# I2C_board_Schematic.net
KiCad netlist of a schematic drawn in Altium Designer
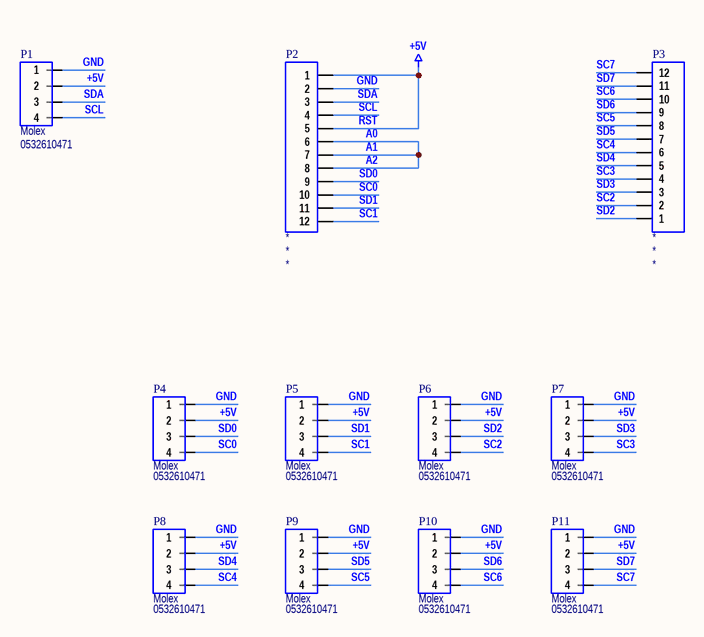
[diagram p0: I2C_board_Schematic.SchDoc]

(export (version "E")
  (design (tool "Eeschema 10.0.6"))
  (components
    (comp (ref "P1")
      (value "CONN MOLEX 53261-0471 (father)")
      (footprint "CONN MOLEX 53261-0471 (father)")
      (fields (field (name "MANUFACTURER") "Molex") (field (name "MODEL") "0532610471"))
      (libsource (lib "ADLibrary_Library") (part "CONN MOLEX 53261-0471 (father)"))
    )
    (comp (ref "P2")
      (value "Connector 1x12 0.1\"")
      (footprint "CONN-12 1x12 MALE")
      (fields (field (name "CASE") "*") (field (name "ALTIUM_VALUE") "*") (field (name "MODEL") "*"))
      (libsource (lib "ADLibrary_Library") (part "Connector 1x12 0.1{dblquote}"))
    )
    (comp (ref "P3")
      (value "Connector 1x12 0.1\"")
      (footprint "CONN-12 1x12 MALE")
      (fields (field (name "CASE") "*") (field (name "ALTIUM_VALUE") "*") (field (name "MODEL") "*"))
      (libsource (lib "") (part "Connector 1x12 0.1{dblquote}_1"))
    )
    (comp (ref "P4")
      (value "CONN MOLEX 53261-0471 (father)")
      (footprint "CONN MOLEX 53261-0471 (father)")
      (fields (field (name "MANUFACTURER") "Molex") (field (name "MODEL") "0532610471"))
      (libsource (lib "ADLibrary_Library") (part "CONN MOLEX 53261-0471 (father)"))
    )
    (comp (ref "P5")
      (value "CONN MOLEX 53261-0471 (father)")
      (footprint "CONN MOLEX 53261-0471 (father)")
      (fields (field (name "MANUFACTURER") "Molex") (field (name "MODEL") "0532610471"))
      (libsource (lib "ADLibrary_Library") (part "CONN MOLEX 53261-0471 (father)"))
    )
    (comp (ref "P6")
      (value "CONN MOLEX 53261-0471 (father)")
      (footprint "CONN MOLEX 53261-0471 (father)")
      (fields (field (name "MANUFACTURER") "Molex") (field (name "MODEL") "0532610471"))
      (libsource (lib "ADLibrary_Library") (part "CONN MOLEX 53261-0471 (father)"))
    )
    (comp (ref "P7")
      (value "CONN MOLEX 53261-0471 (father)")
      (footprint "CONN MOLEX 53261-0471 (father)")
      (fields (field (name "MANUFACTURER") "Molex") (field (name "MODEL") "0532610471"))
      (libsource (lib "ADLibrary_Library") (part "CONN MOLEX 53261-0471 (father)"))
    )
    (comp (ref "P8")
      (value "CONN MOLEX 53261-0471 (father)")
      (footprint "CONN MOLEX 53261-0471 (father)")
      (fields (field (name "MANUFACTURER") "Molex") (field (name "MODEL") "0532610471"))
      (libsource (lib "ADLibrary_Library") (part "CONN MOLEX 53261-0471 (father)"))
    )
    (comp (ref "P9")
      (value "CONN MOLEX 53261-0471 (father)")
      (footprint "CONN MOLEX 53261-0471 (father)")
      (fields (field (name "MANUFACTURER") "Molex") (field (name "MODEL") "0532610471"))
      (libsource (lib "ADLibrary_Library") (part "CONN MOLEX 53261-0471 (father)"))
    )
    (comp (ref "P10")
      (value "CONN MOLEX 53261-0471 (father)")
      (footprint "CONN MOLEX 53261-0471 (father)")
      (fields (field (name "MANUFACTURER") "Molex") (field (name "MODEL") "0532610471"))
      (libsource (lib "ADLibrary_Library") (part "CONN MOLEX 53261-0471 (father)"))
    )
    (comp (ref "P11")
      (value "CONN MOLEX 53261-0471 (father)")
      (footprint "CONN MOLEX 53261-0471 (father)")
      (fields (field (name "MANUFACTURER") "Molex") (field (name "MODEL") "0532610471"))
      (libsource (lib "ADLibrary_Library") (part "CONN MOLEX 53261-0471 (father)"))
    )
  )
  (nets
    (net (code "1") (name "+5V") (class "Default")
      (node (ref "P1") (pin "2") (pinfunction "2_2") (pintype "passive"))
      (node (ref "P10") (pin "2") (pinfunction "2_2") (pintype "passive"))
      (node (ref "P11") (pin "2") (pinfunction "2_2") (pintype "passive"))
      (node (ref "P2") (pin "1") (pinfunction "1_1") (pintype "passive"))
      (node (ref "P2") (pin "5") (pinfunction "5_5") (pintype "passive"))
      (node (ref "P4") (pin "2") (pinfunction "2_2") (pintype "passive"))
      (node (ref "P5") (pin "2") (pinfunction "2_2") (pintype "passive"))
      (node (ref "P6") (pin "2") (pinfunction "2_2") (pintype "passive"))
      (node (ref "P7") (pin "2") (pinfunction "2_2") (pintype "passive"))
      (node (ref "P8") (pin "2") (pinfunction "2_2") (pintype "passive"))
      (node (ref "P9") (pin "2") (pinfunction "2_2") (pintype "passive"))
    )
    (net (code "2") (name "/A0") (class "Default")
      (node (ref "P2") (pin "6") (pinfunction "6_6") (pintype "passive"))
      (node (ref "P2") (pin "7") (pinfunction "7_7") (pintype "passive"))
      (node (ref "P2") (pin "8") (pinfunction "8_8") (pintype "passive"))
    )
    (net (code "3") (name "/GND") (class "Default")
      (node (ref "P1") (pin "1") (pinfunction "1_1") (pintype "passive"))
      (node (ref "P10") (pin "1") (pinfunction "1_1") (pintype "passive"))
      (node (ref "P11") (pin "1") (pinfunction "1_1") (pintype "passive"))
      (node (ref "P2") (pin "2") (pinfunction "2_2") (pintype "passive"))
      (node (ref "P4") (pin "1") (pinfunction "1_1") (pintype "passive"))
      (node (ref "P5") (pin "1") (pinfunction "1_1") (pintype "passive"))
      (node (ref "P6") (pin "1") (pinfunction "1_1") (pintype "passive"))
      (node (ref "P7") (pin "1") (pinfunction "1_1") (pintype "passive"))
      (node (ref "P8") (pin "1") (pinfunction "1_1") (pintype "passive"))
      (node (ref "P9") (pin "1") (pinfunction "1_1") (pintype "passive"))
    )
    (net (code "4") (name "/SC0") (class "Default")
      (node (ref "P2") (pin "10") (pinfunction "10_10") (pintype "passive"))
      (node (ref "P4") (pin "4") (pinfunction "4_4") (pintype "passive"))
    )
    (net (code "5") (name "/SC1") (class "Default")
      (node (ref "P2") (pin "12") (pinfunction "12_12") (pintype "passive"))
      (node (ref "P5") (pin "4") (pinfunction "4_4") (pintype "passive"))
    )
    (net (code "6") (name "/SC2") (class "Default")
      (node (ref "P3") (pin "2") (pinfunction "2_2") (pintype "passive"))
      (node (ref "P6") (pin "4") (pinfunction "4_4") (pintype "passive"))
    )
    (net (code "7") (name "/SC3") (class "Default")
      (node (ref "P3") (pin "4") (pinfunction "4_4") (pintype "passive"))
      (node (ref "P7") (pin "4") (pinfunction "4_4") (pintype "passive"))
    )
    (net (code "8") (name "/SC4") (class "Default")
      (node (ref "P3") (pin "6") (pinfunction "6_6") (pintype "passive"))
      (node (ref "P8") (pin "4") (pinfunction "4_4") (pintype "passive"))
    )
    (net (code "9") (name "/SC5") (class "Default")
      (node (ref "P3") (pin "8") (pinfunction "8_8") (pintype "passive"))
      (node (ref "P9") (pin "4") (pinfunction "4_4") (pintype "passive"))
    )
    (net (code "10") (name "/SC6") (class "Default")
      (node (ref "P10") (pin "4") (pinfunction "4_4") (pintype "passive"))
      (node (ref "P3") (pin "10") (pinfunction "10_10") (pintype "passive"))
    )
    (net (code "11") (name "/SC7") (class "Default")
      (node (ref "P11") (pin "4") (pinfunction "4_4") (pintype "passive"))
      (node (ref "P3") (pin "12") (pinfunction "12_12") (pintype "passive"))
    )
    (net (code "12") (name "/SCL") (class "Default")
      (node (ref "P1") (pin "4") (pinfunction "4_4") (pintype "passive"))
      (node (ref "P2") (pin "4") (pinfunction "4_4") (pintype "passive"))
    )
    (net (code "13") (name "/SD0") (class "Default")
      (node (ref "P2") (pin "9") (pinfunction "9_9") (pintype "passive"))
      (node (ref "P4") (pin "3") (pinfunction "3_3") (pintype "passive"))
    )
    (net (code "14") (name "/SD1") (class "Default")
      (node (ref "P2") (pin "11") (pinfunction "11_11") (pintype "passive"))
      (node (ref "P5") (pin "3") (pinfunction "3_3") (pintype "passive"))
    )
    (net (code "15") (name "/SD2") (class "Default")
      (node (ref "P3") (pin "1") (pinfunction "1_1") (pintype "passive"))
      (node (ref "P6") (pin "3") (pinfunction "3_3") (pintype "passive"))
    )
    (net (code "16") (name "/SD3") (class "Default")
      (node (ref "P3") (pin "3") (pinfunction "3_3") (pintype "passive"))
      (node (ref "P7") (pin "3") (pinfunction "3_3") (pintype "passive"))
    )
    (net (code "17") (name "/SD4") (class "Default")
      (node (ref "P3") (pin "5") (pinfunction "5_5") (pintype "passive"))
      (node (ref "P8") (pin "3") (pinfunction "3_3") (pintype "passive"))
    )
    (net (code "18") (name "/SD5") (class "Default")
      (node (ref "P3") (pin "7") (pinfunction "7_7") (pintype "passive"))
      (node (ref "P9") (pin "3") (pinfunction "3_3") (pintype "passive"))
    )
    (net (code "19") (name "/SD6") (class "Default")
      (node (ref "P10") (pin "3") (pinfunction "3_3") (pintype "passive"))
      (node (ref "P3") (pin "9") (pinfunction "9_9") (pintype "passive"))
    )
    (net (code "20") (name "/SD7") (class "Default")
      (node (ref "P11") (pin "3") (pinfunction "3_3") (pintype "passive"))
      (node (ref "P3") (pin "11") (pinfunction "11_11") (pintype "passive"))
    )
    (net (code "21") (name "/SDA") (class "Default")
      (node (ref "P1") (pin "3") (pinfunction "3_3") (pintype "passive"))
      (node (ref "P2") (pin "3") (pinfunction "3_3") (pintype "passive"))
    )
  )
)
